# hashlet_pi.net
KiCad netlist of a schematic drawn in EAGLE
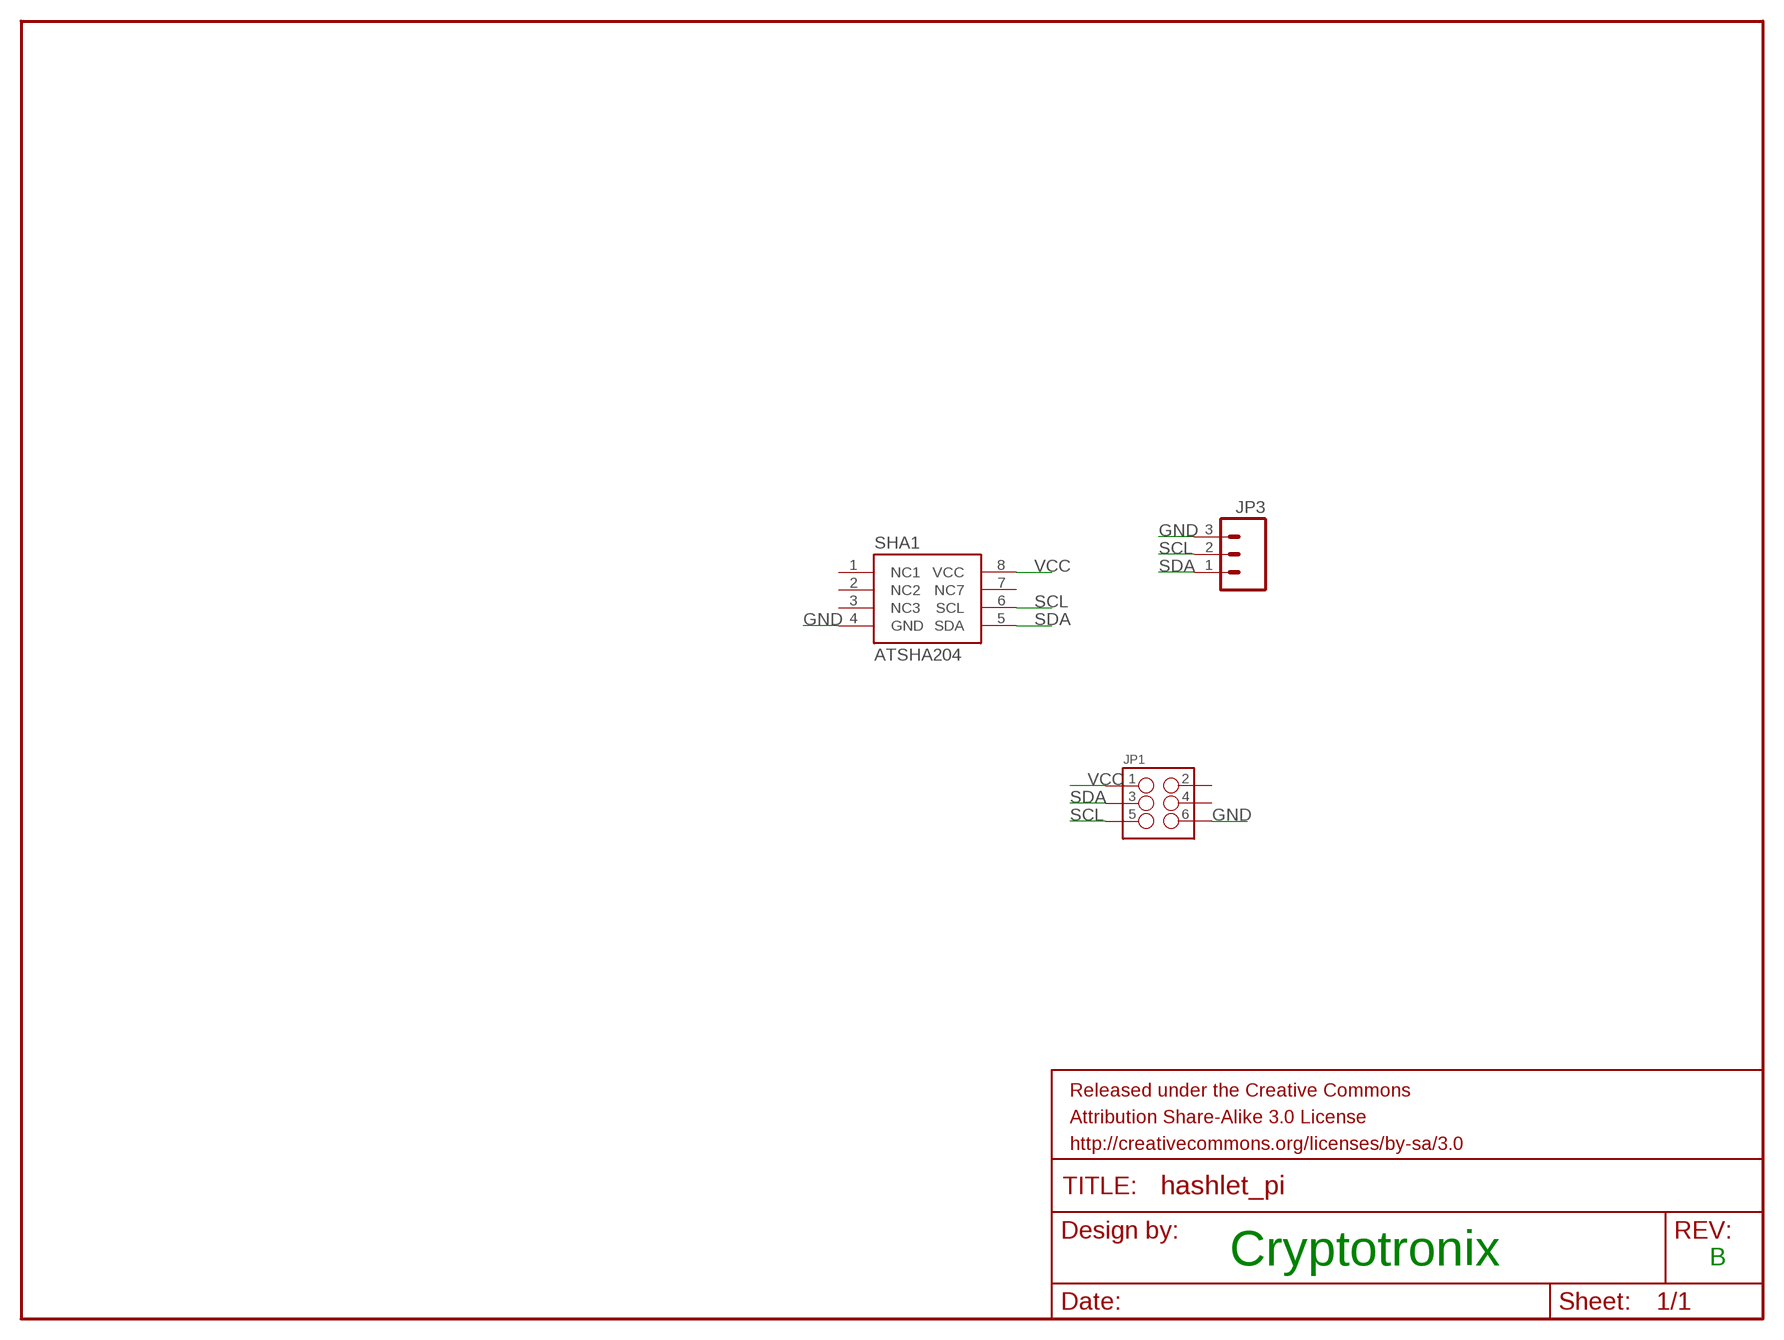
[diagram p0: schematic, sheet 1]

(export (version "E")
  (design (tool "Eeschema 10.0.6"))
  (components
    (comp (ref "FRAME1")
      (value "FRAME-LETTER")
      (footprint "eagle-import:CREATIVE_COMMONS")
      (libsource (lib "eagle-import") (part "FRAME-LETTER"))
    )
    (comp (ref "JP1")
      (value "M03X22X3_SILK_SM")
      (footprint "eagle-import:2X3")
      (libsource (lib "eagle-import") (part "M03X22X3_SILK_SM"))
    )
    (comp (ref "JP3")
      (value "M03PTH")
      (footprint "eagle-import:1X03")
      (libsource (lib "eagle-import") (part "M03PTH"))
    )
    (comp (ref "SHA1")
      (value "ATSHA204")
      (footprint "eagle-import:SOIC8")
      (libsource (lib "eagle-import") (part "ATSHA204"))
    )
  )
  (nets
    (net (code "1") (name "/GND") (class "Default")
      (node (ref "JP1") (pin "6") (pinfunction "6_6") (pintype "bidirectional"))
      (node (ref "JP3") (pin "3") (pinfunction "3_3") (pintype "passive"))
      (node (ref "SHA1") (pin "4") (pinfunction "GND_4") (pintype "power_in"))
    )
    (net (code "2") (name "/SCL") (class "Default")
      (node (ref "JP1") (pin "5") (pinfunction "5_5") (pintype "bidirectional"))
      (node (ref "JP3") (pin "2") (pinfunction "2_2") (pintype "passive"))
      (node (ref "SHA1") (pin "6") (pinfunction "SCL_6") (pintype "bidirectional"))
    )
    (net (code "3") (name "/SDA") (class "Default")
      (node (ref "JP1") (pin "3") (pinfunction "3_3") (pintype "bidirectional"))
      (node (ref "JP3") (pin "1") (pinfunction "1_1") (pintype "passive"))
      (node (ref "SHA1") (pin "5") (pinfunction "SDA_5") (pintype "bidirectional"))
    )
    (net (code "4") (name "/VCC") (class "Default")
      (node (ref "JP1") (pin "1") (pinfunction "1_1") (pintype "bidirectional"))
      (node (ref "SHA1") (pin "8") (pinfunction "VCC_8") (pintype "power_in"))
    )
    (net (code "5") (name "unconnected-(JP1-Pad2)") (class "Default")
      (node (ref "JP1") (pin "2") (pinfunction "2_2") (pintype "bidirectional"))
    )
    (net (code "6") (name "unconnected-(JP1-Pad4)") (class "Default")
      (node (ref "JP1") (pin "4") (pinfunction "4_4") (pintype "bidirectional"))
    )
    (net (code "7") (name "unconnected-(SHA1-NC1-Pad1)") (class "Default")
      (node (ref "SHA1") (pin "1") (pinfunction "NC1_1") (pintype "no_connect"))
    )
    (net (code "8") (name "unconnected-(SHA1-NC2-Pad2)") (class "Default")
      (node (ref "SHA1") (pin "2") (pinfunction "NC2_2") (pintype "no_connect"))
    )
    (net (code "9") (name "unconnected-(SHA1-NC3-Pad3)") (class "Default")
      (node (ref "SHA1") (pin "3") (pinfunction "NC3_3") (pintype "no_connect"))
    )
    (net (code "10") (name "unconnected-(SHA1-NC7-Pad7)") (class "Default")
      (node (ref "SHA1") (pin "7") (pinfunction "NC7_7") (pintype "no_connect"))
    )
  )
)
